# DC-link.net
KiCad netlist of a schematic drawn in Altium Designer
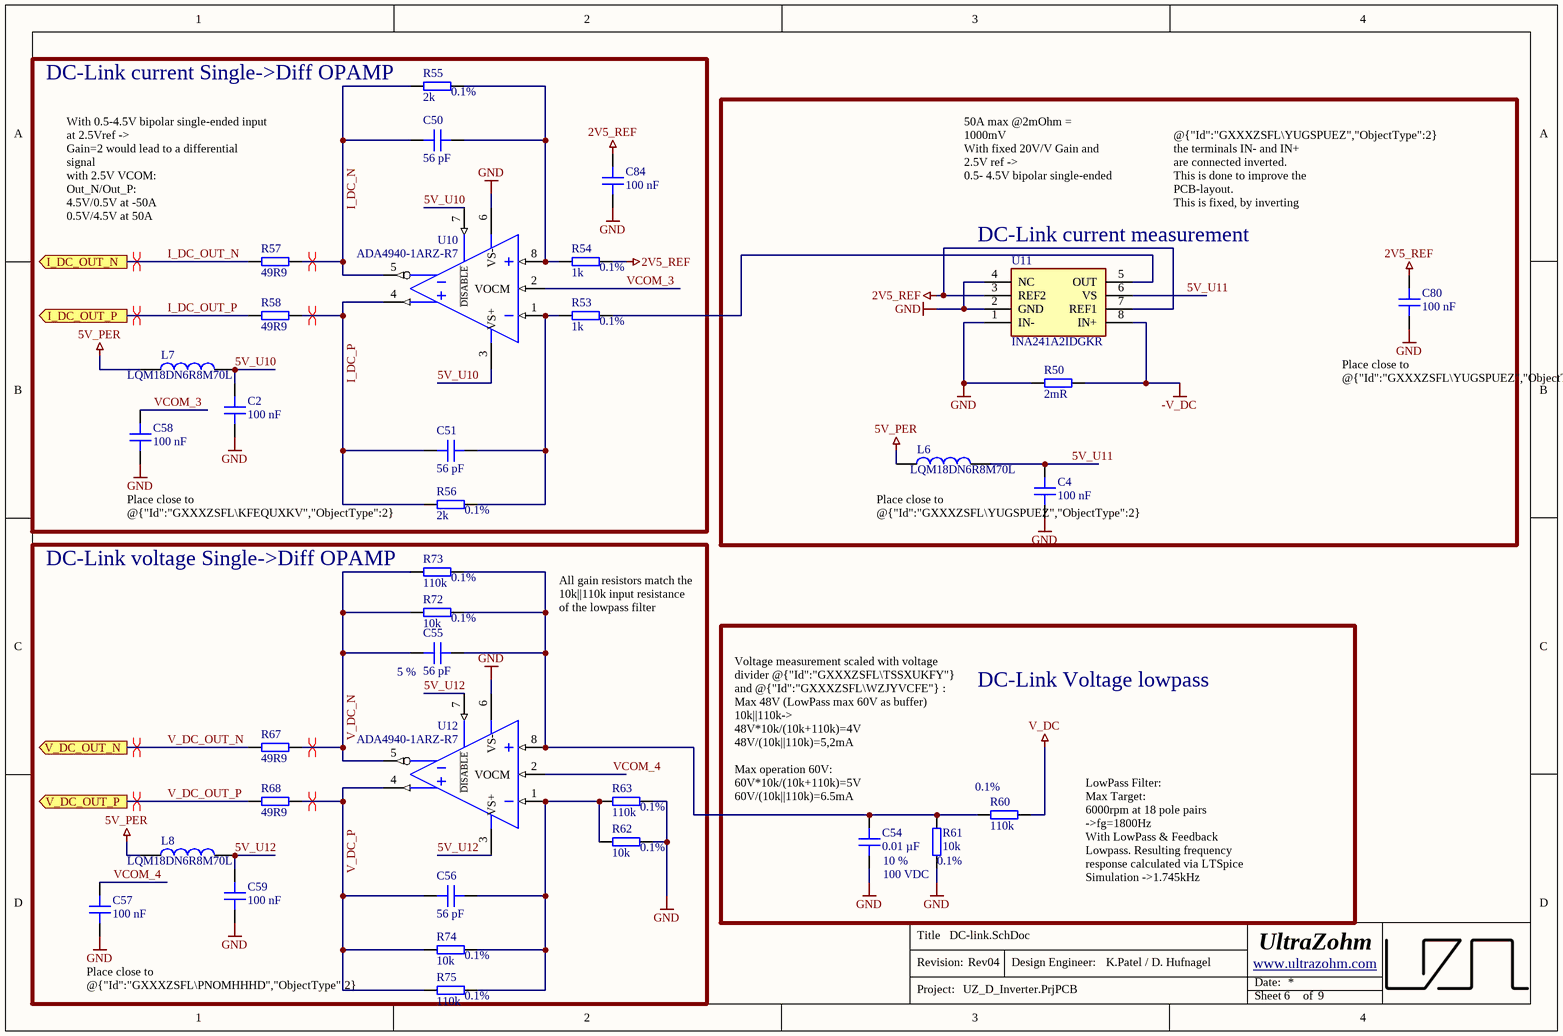
[diagram p0: DC-link.SchDoc]

(export (version "E")
  (design (tool "Eeschema 10.0.6"))
  (components
    (comp (ref "C2")
      (value "100 nF")
      (footprint "C_0603")
      (description "100V 100nF X7S ±10% 0603 Multilayer Ceramic Capacitors MLCC - SMD/SMT ROHS")
      (fields
        (field (name "MANUFACTURER PART NUMBER") "C1608X7S2A104KT000N")
        (field (name "MANUFACTURER") "TDK")
        (field (name "CREATED FROM") "AGeiger")
      )
      (libsource (lib "user") (part "Capacitor"))
    )
    (comp (ref "C4")
      (value "100 nF")
      (footprint "C_0603")
      (description "100V 100nF X7S ±10% 0603 Multilayer Ceramic Capacitors MLCC - SMD/SMT ROHS")
      (fields
        (field (name "MANUFACTURER PART NUMBER") "C1608X7S2A104KT000N")
        (field (name "MANUFACTURER") "TDK")
        (field (name "CREATED FROM") "AGeiger")
      )
      (libsource (lib "user") (part "Capacitor"))
    )
    (comp (ref "C50")
      (value "56 pF")
      (footprint "C_0603")
      (description "Capacitor 0603, 50 VDC, 56 pF, C0G")
      (fields
        (field (name "MANUFACTURER PART NUMBER") "CL10C560JB8NNNC")
        (field (name "MANUFACTURER") "Samsung Electro-Mechanics")
        (field (name "CREATED FROM") "DHufnagel")
      )
      (libsource (lib "user") (part "Capacitor"))
    )
    (comp (ref "C51")
      (value "56 pF")
      (footprint "C_0603")
      (description "Capacitor 0603, 50 VDC, 56 pF, C0G")
      (fields
        (field (name "MANUFACTURER PART NUMBER") "CL10C560JB8NNNC")
        (field (name "MANUFACTURER") "Samsung Electro-Mechanics")
        (field (name "CREATED FROM") "DHufnagel")
      )
      (libsource (lib "user") (part "Capacitor"))
    )
    (comp (ref "C54")
      (value "0.01 µF")
      (footprint "C_0805")
      (description "100V 10nF 0805 Multilayer Ceramic Capacitors MLCC - SMD/SMT ROHS")
      (fields
        (field (name "MANUFACTURER PART NUMBER") "HV0805X7R103K101NT")
        (field (name "MANUFACTURER") "AIDE")
        (field (name "TOLERANCE") "10 %")
        (field (name "VOLTAGE RATING") "100 VDC")
        (field (name "CREATED FROM") "KIlhan")
      )
      (libsource (lib "user") (part "Capacitor"))
    )
    (comp (ref "C55")
      (value "56 pF")
      (footprint "C_0603")
      (description "Capacitor 0603, 50 VDC, 56 pF, C0G")
      (fields
        (field (name "MANUFACTURER PART NUMBER") "CL10C560JB8NNNC")
        (field (name "MANUFACTURER") "Samsung Electro-Mechanics")
        (field (name "TOLERANCE") "5 %")
        (field (name "CREATED FROM") "DHufnagel")
      )
      (libsource (lib "user") (part "Capacitor"))
    )
    (comp (ref "C56")
      (value "56 pF")
      (footprint "C_0603")
      (description "Capacitor 0603, 50 VDC, 56 pF, C0G")
      (fields
        (field (name "MANUFACTURER PART NUMBER") "CL10C560JB8NNNC")
        (field (name "MANUFACTURER") "Samsung Electro-Mechanics")
        (field (name "CREATED FROM") "DHufnagel")
      )
      (libsource (lib "user") (part "Capacitor"))
    )
    (comp (ref "C57")
      (value "100 nF")
      (footprint "C_0603")
      (description "100V 100nF X7S ±10% 0603 Multilayer Ceramic Capacitors MLCC - SMD/SMT ROHS")
      (fields
        (field (name "MANUFACTURER PART NUMBER") "C1608X7S2A104KT000N")
        (field (name "MANUFACTURER") "TDK")
        (field (name "CREATED FROM") "AGeiger")
      )
      (libsource (lib "user") (part "Capacitor"))
    )
    (comp (ref "C58")
      (value "100 nF")
      (footprint "C_0603")
      (description "100V 100nF X7S ±10% 0603 Multilayer Ceramic Capacitors MLCC - SMD/SMT ROHS")
      (fields
        (field (name "MANUFACTURER PART NUMBER") "C1608X7S2A104KT000N")
        (field (name "MANUFACTURER") "TDK")
        (field (name "CREATED FROM") "AGeiger")
      )
      (libsource (lib "user") (part "Capacitor"))
    )
    (comp (ref "C59")
      (value "100 nF")
      (footprint "C_0603")
      (description "100V 100nF X7S ±10% 0603 Multilayer Ceramic Capacitors MLCC - SMD/SMT ROHS")
      (fields
        (field (name "MANUFACTURER PART NUMBER") "C1608X7S2A104KT000N")
        (field (name "MANUFACTURER") "TDK")
        (field (name "CREATED FROM") "AGeiger")
      )
      (libsource (lib "user") (part "Capacitor"))
    )
    (comp (ref "C80")
      (value "100 nF")
      (footprint "C_0603")
      (description "100V 100nF X7S ±10% 0603 Multilayer Ceramic Capacitors MLCC - SMD/SMT ROHS")
      (fields
        (field (name "MANUFACTURER PART NUMBER") "C1608X7S2A104KT000N")
        (field (name "MANUFACTURER") "TDK")
        (field (name "CREATED FROM") "AGeiger")
      )
      (libsource (lib "user") (part "Capacitor"))
    )
    (comp (ref "C84")
      (value "100 nF")
      (footprint "C_0603")
      (description "100V 100nF X7S ±10% 0603 Multilayer Ceramic Capacitors MLCC - SMD/SMT ROHS")
      (fields
        (field (name "MANUFACTURER PART NUMBER") "C1608X7S2A104KT000N")
        (field (name "MANUFACTURER") "TDK")
        (field (name "CREATED FROM") "AGeiger")
      )
      (libsource (lib "user") (part "Capacitor"))
    )
    (comp (ref "L6")
      (value "LQM18DN6R8M70L")
      (footprint "INDC1608X95N")
      (description "6.8µH, 120mA, 0603, 740mOhm, 20%")
      (fields
        (field (name "MF") "EPCOS / TDK")
        (field (name "MPN") "B82464G4154M")
        (field (name "CREATED FROM") "DHufnagel")
      )
      (libsource (lib "user") (part "B82464G4154M"))
    )
    (comp (ref "L7")
      (value "LQM18DN6R8M70L")
      (footprint "INDC1608X95N")
      (description "6.8µH, 120mA, 0603, 740mOhm, 20%")
      (fields
        (field (name "MF") "EPCOS / TDK")
        (field (name "MPN") "B82464G4154M")
        (field (name "CREATED FROM") "DHufnagel")
      )
      (libsource (lib "user") (part "B82464G4154M"))
    )
    (comp (ref "L8")
      (value "LQM18DN6R8M70L")
      (footprint "INDC1608X95N")
      (description "6.8µH, 120mA, 0603, 740mOhm, 20%")
      (fields
        (field (name "MF") "EPCOS / TDK")
        (field (name "MPN") "B82464G4154M")
        (field (name "CREATED FROM") "DHufnagel")
      )
      (libsource (lib "user") (part "B82464G4154M"))
    )
    (comp (ref "R50")
      (value "2mR")
      (footprint "3921")
      (description "Shunt resistor 2mOhm, 5W, 1%")
      (fields
        (field (name "MANUFACTURER PART NUMBER") "WSL39212L000FEA")
        (field (name "MANUFACTURER") "Vishay")
        (field (name "CREATED FROM") "DHufnagel")
      )
      (libsource (lib "user") (part "Resistor"))
    )
    (comp (ref "R53")
      (value "1k")
      (footprint "RES 0603_1608")
      (description "SMD resistor 0.1%")
      (fields
        (field (name "MANUFACTURER PART NUMBER") "PCF-W0603LF-03-1001-B-P-LT")
        (field (name "MANUFACTURER") "IRC / TT Electronics")
        (field (name "TOLERANCE") "0.1%")
        (field (name "CREATED FROM") "MGremer")
      )
      (libsource (lib "user") (part "Resistor"))
    )
    (comp (ref "R54")
      (value "1k")
      (footprint "RES 0603_1608")
      (description "SMD resistor 0.1%")
      (fields
        (field (name "MANUFACTURER PART NUMBER") "PCF-W0603LF-03-1001-B-P-LT")
        (field (name "MANUFACTURER") "IRC / TT Electronics")
        (field (name "TOLERANCE") "0.1%")
        (field (name "CREATED FROM") "MGremer")
      )
      (libsource (lib "user") (part "Resistor"))
    )
    (comp (ref "R55")
      (value "2k")
      (footprint "RES 0603_1608")
      (description "SMD resistor 0.1%")
      (fields
        (field (name "MANUFACTURER PART NUMBER") "ERJ-PB3B2001V")
        (field (name "MANUFACTURER") "Panasonic")
        (field (name "TOLERANCE") "0.1%")
        (field (name "CREATED FROM") "DHufnagel")
      )
      (libsource (lib "user") (part "Resistor"))
    )
    (comp (ref "R56")
      (value "2k")
      (footprint "RES 0603_1608")
      (description "SMD resistor 0.1%")
      (fields
        (field (name "MANUFACTURER PART NUMBER") "ERJ-PB3B2001V")
        (field (name "MANUFACTURER") "Panasonic")
        (field (name "TOLERANCE") "0.1%")
        (field (name "CREATED FROM") "DHufnagel")
      )
      (libsource (lib "user") (part "Resistor"))
    )
    (comp (ref "R57")
      (value "49R9")
      (footprint "RES 0603_1608")
      (description "SMD resistor 1%")
      (fields
        (field (name "MANUFACTURER PART NUMBER") "RK73H1JTTD49R9F")
        (field (name "MANUFACTURER") "KOA Speer")
        (field (name "CREATED FROM") "DHufnagel")
      )
      (libsource (lib "user") (part "Resistor"))
    )
    (comp (ref "R58")
      (value "49R9")
      (footprint "RES 0603_1608")
      (description "SMD resistor 1%")
      (fields
        (field (name "MANUFACTURER PART NUMBER") "RK73H1JTTD49R9F")
        (field (name "MANUFACTURER") "KOA Speer")
        (field (name "CREATED FROM") "DHufnagel")
      )
      (libsource (lib "user") (part "Resistor"))
    )
    (comp (ref "R60")
      (value "110k")
      (footprint "RES 0603_1608")
      (description "SMD resistor 0.1%, 10ppm")
      (fields
        (field (name "MANUFACTURER PART NUMBER") "RQ73C1J110KBTD")
        (field (name "MANUFACTURER") "TE Connectivity / Holsworthy")
        (field (name "TOLERANCE") "0.1%")
        (field (name "CREATED FROM") "DHufnagel")
      )
      (libsource (lib "user") (part "Resistor"))
    )
    (comp (ref "R61")
      (value "10k")
      (footprint "RES 0603_1608")
      (description "SMD resistor 0.1%, 10ppm")
      (fields
        (field (name "MANUFACTURER PART NUMBER") "RQ73C1J10KBTD")
        (field (name "MANUFACTURER") "TE Connectivity")
        (field (name "CREATED FROM") "DHufnagel")
      )
      (libsource (lib "user") (part "Resistor"))
    )
    (comp (ref "R62")
      (value "10k")
      (footprint "RES 0603_1608")
      (description "SMD resistor 0.1%, 10ppm")
      (fields
        (field (name "MANUFACTURER PART NUMBER") "RQ73C1J10KBTD")
        (field (name "MANUFACTURER") "TE Connectivity")
        (field (name "TOLERANCE") "0.1%")
        (field (name "CREATED FROM") "DHufnagel")
      )
      (libsource (lib "user") (part "Resistor"))
    )
    (comp (ref "R63")
      (value "110k")
      (footprint "RES 0603_1608")
      (description "SMD resistor 0.1%, 10ppm")
      (fields
        (field (name "MANUFACTURER PART NUMBER") "RQ73C1J110KBTD")
        (field (name "MANUFACTURER") "TE Connectivity / Holsworthy")
        (field (name "TOLERANCE") "0.1%")
        (field (name "CREATED FROM") "DHufnagel")
      )
      (libsource (lib "user") (part "Resistor"))
    )
    (comp (ref "R67")
      (value "49R9")
      (footprint "RES 0603_1608")
      (description "SMD resistor 1%")
      (fields
        (field (name "MANUFACTURER PART NUMBER") "RK73H1JTTD49R9F")
        (field (name "MANUFACTURER") "KOA Speer")
        (field (name "CREATED FROM") "DHufnagel")
      )
      (libsource (lib "user") (part "Resistor"))
    )
    (comp (ref "R68")
      (value "49R9")
      (footprint "RES 0603_1608")
      (description "SMD resistor 1%")
      (fields
        (field (name "MANUFACTURER PART NUMBER") "RK73H1JTTD49R9F")
        (field (name "MANUFACTURER") "KOA Speer")
        (field (name "CREATED FROM") "DHufnagel")
      )
      (libsource (lib "user") (part "Resistor"))
    )
    (comp (ref "R72")
      (value "10k")
      (footprint "RES 0603_1608")
      (description "SMD resistor 0.1%, 10ppm")
      (fields
        (field (name "MANUFACTURER PART NUMBER") "RQ73C1J10KBTD")
        (field (name "MANUFACTURER") "TE Connectivity")
        (field (name "TOLERANCE") "0.1%")
        (field (name "CREATED FROM") "DHufnagel")
      )
      (libsource (lib "user") (part "Resistor"))
    )
    (comp (ref "R73")
      (value "110k")
      (footprint "RES 0603_1608")
      (description "SMD resistor 0.1%, 10ppm")
      (fields
        (field (name "MANUFACTURER PART NUMBER") "RQ73C1J110KBTD")
        (field (name "MANUFACTURER") "TE Connectivity / Holsworthy")
        (field (name "TOLERANCE") "0.1%")
        (field (name "CREATED FROM") "DHufnagel")
      )
      (libsource (lib "user") (part "Resistor"))
    )
    (comp (ref "R74")
      (value "10k")
      (footprint "RES 0603_1608")
      (description "SMD resistor 0.1%, 10ppm")
      (fields
        (field (name "MANUFACTURER PART NUMBER") "RQ73C1J10KBTD")
        (field (name "MANUFACTURER") "TE Connectivity")
        (field (name "TOLERANCE") "0.1%")
        (field (name "CREATED FROM") "DHufnagel")
      )
      (libsource (lib "user") (part "Resistor"))
    )
    (comp (ref "R75")
      (value "110k")
      (footprint "RES 0603_1608")
      (description "SMD resistor 0.1%, 10ppm")
      (fields
        (field (name "MANUFACTURER PART NUMBER") "RQ73C1J110KBTD")
        (field (name "MANUFACTURER") "TE Connectivity / Holsworthy")
        (field (name "TOLERANCE") "0.1%")
        (field (name "CREATED FROM") "DHufnagel")
      )
      (libsource (lib "user") (part "Resistor"))
    )
    (comp (ref "U10")
      (value "ADA4940-1ARZ-R7")
      (footprint "SOT127P600X175-8N")
      (description "Fully Differential Amplifier, Ultralow-Power,Low Distortion, 260-MHz")
      (fields
        (field (name "MANUFACTURER") "Analog Devices")
        (field (name "LCSC PART NUMBER") "C730049")
        (field (name "CREATED FROM") "DHufnagel")
      )
      (libsource (lib "user") (part "ADA4940-1ARZ"))
    )
    (comp (ref "U11")
      (value "INA241A2IDGKR")
      (footprint "SOP65P490X110-8N")
      (description "Current Sense Amplifier, 5-100 V  CMV, 20 V/V, bidirectional")
      (fields (field (name "MANUFACTURER") "Texas Instruments") (field (name "CREATED FROM") "KPatel"))
      (libsource (lib "user") (part "INA241A2IDGKR"))
    )
    (comp (ref "U12")
      (value "ADA4940-1ARZ-R7")
      (footprint "SOT127P600X175-8N")
      (description "Fully Differential Amplifier, Ultralow-Power,Low Distortion, 260-MHz")
      (fields
        (field (name "MANUFACTURER") "Analog Devices")
        (field (name "LCSC PART NUMBER") "C730049")
        (field (name "CREATED FROM") "DHufnagel")
      )
      (libsource (lib "user") (part "ADA4940-1ARZ"))
    )
  )
  (nets
    (net (code "1") (name "-V_DC") (class "Default")
      (node (ref "R50") (pin "2") (pinfunction "2_2") (pintype "passive"))
      (node (ref "U11") (pin "8") (pinfunction "IN+_8") (pintype "passive"))
    )
    (net (code "2") (name "/5V_U10") (class "Default")
      (node (ref "C2") (pin "2") (pinfunction "2_2") (pintype "passive"))
      (node (ref "L7") (pin "2") (pinfunction "2_2") (pintype "passive"))
      (node (ref "U10") (pin "3") (pinfunction "VS+_3") (pintype "power_in"))
      (node (ref "U10") (pin "7") (pinfunction "~{DISABLE}_7") (pintype "input"))
    )
    (net (code "3") (name "/5V_U11") (class "Default")
      (node (ref "C4") (pin "2") (pinfunction "2_2") (pintype "passive"))
      (node (ref "L6") (pin "2") (pinfunction "2_2") (pintype "passive"))
      (node (ref "U11") (pin "6") (pinfunction "VS_6") (pintype "passive"))
    )
    (net (code "4") (name "/5V_U12") (class "Default")
      (node (ref "C59") (pin "2") (pinfunction "2_2") (pintype "passive"))
      (node (ref "L8") (pin "2") (pinfunction "2_2") (pintype "passive"))
      (node (ref "U12") (pin "3") (pinfunction "VS+_3") (pintype "power_in"))
      (node (ref "U12") (pin "7") (pinfunction "~{DISABLE}_7") (pintype "input"))
    )
    (net (code "5") (name "/I_DC_N") (class "Default")
      (node (ref "C50") (pin "1") (pinfunction "1_1") (pintype "passive"))
      (node (ref "R55") (pin "1") (pinfunction "1_1") (pintype "passive"))
      (node (ref "R57") (pin "2") (pinfunction "2_2") (pintype "passive"))
      (node (ref "U10") (pin "5") (pinfunction "VOUT-_5") (pintype "output"))
    )
    (net (code "6") (name "/I_DC_OUT_N") (class "Default")
      (node (ref "R57") (pin "1") (pinfunction "1_1") (pintype "passive"))
    )
    (net (code "7") (name "/I_DC_OUT_P") (class "Default")
      (node (ref "R58") (pin "1") (pinfunction "1_1") (pintype "passive"))
    )
    (net (code "8") (name "/I_DC_P") (class "Default")
      (node (ref "C51") (pin "2") (pinfunction "2_2") (pintype "passive"))
      (node (ref "R56") (pin "2") (pinfunction "2_2") (pintype "passive"))
      (node (ref "R58") (pin "2") (pinfunction "2_2") (pintype "passive"))
      (node (ref "U10") (pin "4") (pinfunction "VOUT+_4") (pintype "output"))
    )
    (net (code "9") (name "/VCOM_3") (class "Default")
      (node (ref "C58") (pin "2") (pinfunction "2_2") (pintype "passive"))
      (node (ref "U10") (pin "2") (pinfunction "VOCM_2") (pintype "input"))
    )
    (net (code "10") (name "/VCOM_4") (class "Default")
      (node (ref "C57") (pin "2") (pinfunction "2_2") (pintype "passive"))
      (node (ref "U12") (pin "2") (pinfunction "VOCM_2") (pintype "input"))
    )
    (net (code "11") (name "/V_DC_N") (class "Default")
      (node (ref "C55") (pin "1") (pinfunction "1_1") (pintype "passive"))
      (node (ref "R67") (pin "2") (pinfunction "2_2") (pintype "passive"))
      (node (ref "R72") (pin "2") (pinfunction "2_2") (pintype "passive"))
      (node (ref "R73") (pin "1") (pinfunction "1_1") (pintype "passive"))
      (node (ref "U12") (pin "5") (pinfunction "VOUT-_5") (pintype "output"))
    )
    (net (code "12") (name "/V_DC_OUT_N") (class "Default")
      (node (ref "R67") (pin "1") (pinfunction "1_1") (pintype "passive"))
    )
    (net (code "13") (name "/V_DC_OUT_P") (class "Default")
      (node (ref "R68") (pin "1") (pinfunction "1_1") (pintype "passive"))
    )
    (net (code "14") (name "/V_DC_P") (class "Default")
      (node (ref "C56") (pin "2") (pinfunction "2_2") (pintype "passive"))
      (node (ref "R68") (pin "2") (pinfunction "2_2") (pintype "passive"))
      (node (ref "R74") (pin "2") (pinfunction "2_2") (pintype "passive"))
      (node (ref "R75") (pin "1") (pinfunction "1_1") (pintype "passive"))
      (node (ref "U12") (pin "4") (pinfunction "VOUT+_4") (pintype "output"))
    )
    (net (code "15") (name "2V5_REF") (class "Default")
      (node (ref "C80") (pin "2") (pinfunction "2_2") (pintype "passive"))
      (node (ref "C84") (pin "2") (pinfunction "2_2") (pintype "passive"))
      (node (ref "R54") (pin "2") (pinfunction "2_2") (pintype "passive"))
      (node (ref "U11") (pin "3") (pinfunction "REF2_3") (pintype "passive"))
      (node (ref "U11") (pin "7") (pinfunction "REF1_7") (pintype "passive"))
    )
    (net (code "16") (name "5V_PER") (class "Default")
      (node (ref "L6") (pin "1") (pinfunction "1_1") (pintype "passive"))
      (node (ref "L7") (pin "1") (pinfunction "1_1") (pintype "passive"))
      (node (ref "L8") (pin "1") (pinfunction "1_1") (pintype "passive"))
    )
    (net (code "17") (name "GND") (class "Default")
      (node (ref "C2") (pin "1") (pinfunction "1_1") (pintype "passive"))
      (node (ref "C4") (pin "1") (pinfunction "1_1") (pintype "passive"))
      (node (ref "C54") (pin "1") (pinfunction "1_1") (pintype "passive"))
      (node (ref "C57") (pin "1") (pinfunction "1_1") (pintype "passive"))
      (node (ref "C58") (pin "1") (pinfunction "1_1") (pintype "passive"))
      (node (ref "C59") (pin "1") (pinfunction "1_1") (pintype "passive"))
      (node (ref "C80") (pin "1") (pinfunction "1_1") (pintype "passive"))
      (node (ref "C84") (pin "1") (pinfunction "1_1") (pintype "passive"))
      (node (ref "R50") (pin "1") (pinfunction "1_1") (pintype "passive"))
      (node (ref "R61") (pin "1") (pinfunction "1_1") (pintype "passive"))
      (node (ref "R62") (pin "1") (pinfunction "1_1") (pintype "passive"))
      (node (ref "R63") (pin "2") (pinfunction "2_2") (pintype "passive"))
      (node (ref "U10") (pin "6") (pinfunction "VS-_6") (pintype "power_in"))
      (node (ref "U11") (pin "1") (pinfunction "IN-_1") (pintype "passive"))
      (node (ref "U11") (pin "2") (pinfunction "GND_2") (pintype "passive"))
      (node (ref "U11") (pin "4") (pinfunction "NC_4") (pintype "passive"))
      (node (ref "U12") (pin "6") (pinfunction "VS-_6") (pintype "power_in"))
    )
    (net (code "18") (name "Net-(U10-VIN+)") (class "Default")
      (node (ref "C50") (pin "2") (pinfunction "2_2") (pintype "passive"))
      (node (ref "R54") (pin "1") (pinfunction "1_1") (pintype "passive"))
      (node (ref "R55") (pin "2") (pinfunction "2_2") (pintype "passive"))
      (node (ref "U10") (pin "8") (pinfunction "VIN+_8") (pintype "input"))
    )
    (net (code "19") (name "Net-(U10-VIN-)") (class "Default")
      (node (ref "C51") (pin "1") (pinfunction "1_1") (pintype "passive"))
      (node (ref "R53") (pin "1") (pinfunction "1_1") (pintype "passive"))
      (node (ref "R56") (pin "1") (pinfunction "1_1") (pintype "passive"))
      (node (ref "U10") (pin "1") (pinfunction "VIN-_1") (pintype "input"))
    )
    (net (code "20") (name "Net-(U11-OUT)") (class "Default")
      (node (ref "R53") (pin "2") (pinfunction "2_2") (pintype "passive"))
      (node (ref "U11") (pin "5") (pinfunction "OUT_5") (pintype "passive"))
    )
    (net (code "21") (name "Net-(U12-VIN+)") (class "Default")
      (node (ref "C54") (pin "2") (pinfunction "2_2") (pintype "passive"))
      (node (ref "C55") (pin "2") (pinfunction "2_2") (pintype "passive"))
      (node (ref "R60") (pin "1") (pinfunction "1_1") (pintype "passive"))
      (node (ref "R61") (pin "2") (pinfunction "2_2") (pintype "passive"))
      (node (ref "R72") (pin "1") (pinfunction "1_1") (pintype "passive"))
      (node (ref "R73") (pin "2") (pinfunction "2_2") (pintype "passive"))
      (node (ref "U12") (pin "8") (pinfunction "VIN+_8") (pintype "input"))
    )
    (net (code "22") (name "Net-(U12-VIN-)") (class "Default")
      (node (ref "C56") (pin "1") (pinfunction "1_1") (pintype "passive"))
      (node (ref "R62") (pin "2") (pinfunction "2_2") (pintype "passive"))
      (node (ref "R63") (pin "1") (pinfunction "1_1") (pintype "passive"))
      (node (ref "R74") (pin "1") (pinfunction "1_1") (pintype "passive"))
      (node (ref "R75") (pin "2") (pinfunction "2_2") (pintype "passive"))
      (node (ref "U12") (pin "1") (pinfunction "VIN-_1") (pintype "input"))
    )
    (net (code "23") (name "V_DC") (class "Default")
      (node (ref "R60") (pin "2") (pinfunction "2_2") (pintype "passive"))
    )
  )
)
